# STEERING_WHEEL_SWITCHES_V2_CONTROLLER.net
KiCad netlist of a schematic drawn in Altium Designer
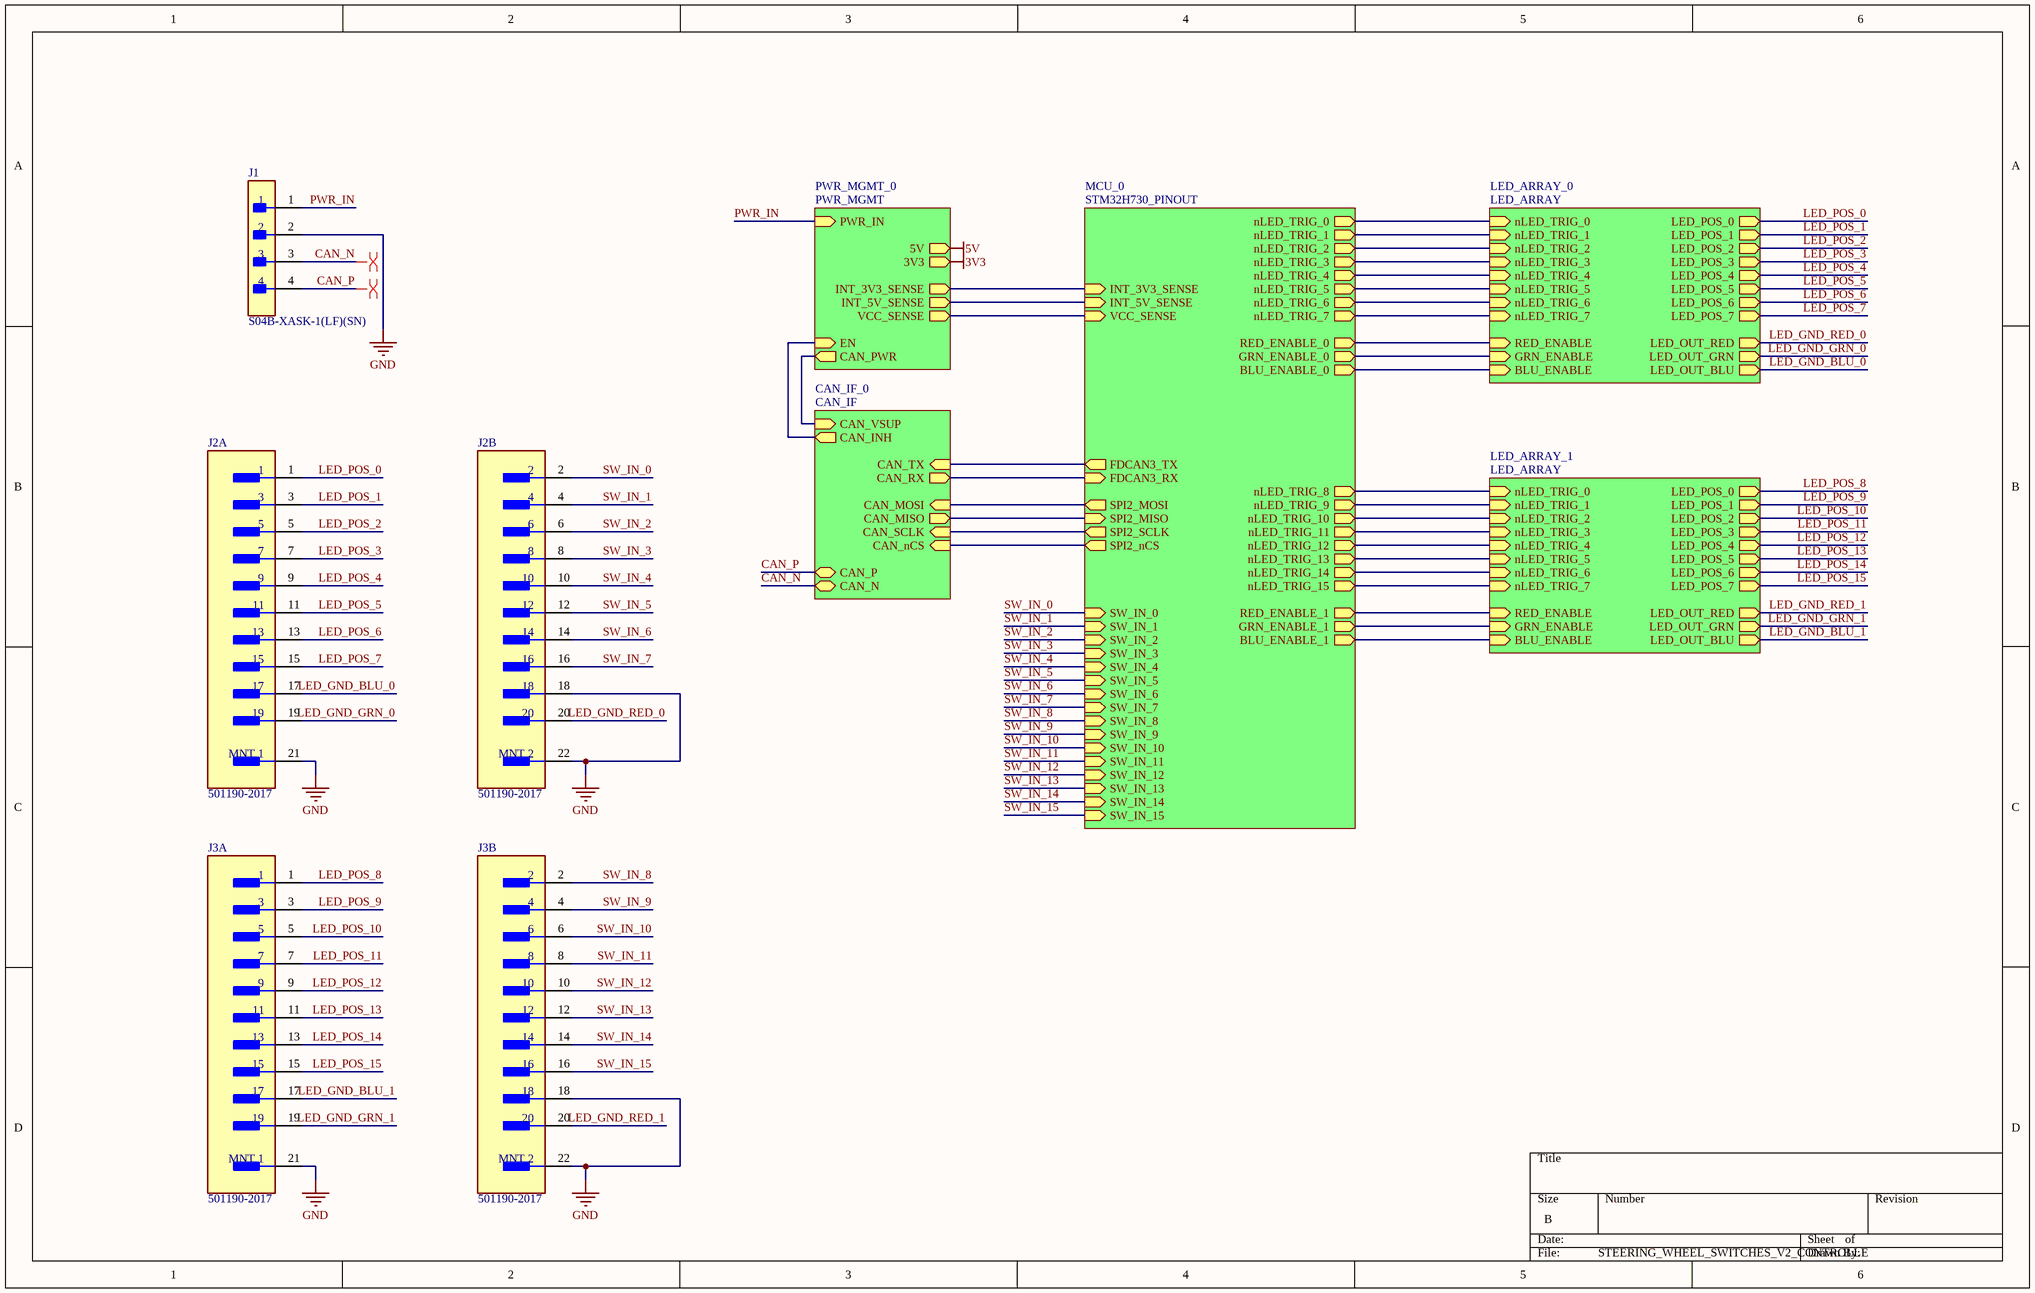
[diagram p0: STEERING_WHEEL_SWITCHES_V2_CONTROLLER.SchDoc]

(export (version "E")
  (design (tool "Eeschema 10.0.6"))
  (components
    (comp (ref "J1")
      (value "S04B-XASK-1(LF)(SN)")
      (footprint "FP-S04B-XASK-1_LF_SN-MFG")
      (description "CONN HEADER R/A 4POS 2.5MM")
      (libsource (lib "Altium Content Vault") (part "299a8cea1bdcbc3624fe62c390fa72c"))
    )
    (comp (ref "J2")
      (value "501190-2017")
      (footprint "FP-501190-2017-MFG")
      (description "CONN HEADER SMD 20POS 1MM")
      (libsource (lib "Altium Content Vault") (part "3088fde206a7053fe950ea66454f304"))
    )
    (comp (ref "J3")
      (value "501190-2017")
      (footprint "FP-501190-2017-MFG")
      (description "CONN HEADER SMD 20POS 1MM")
      (libsource (lib "Altium Content Vault") (part "3088fde206a7053fe950ea66454f304"))
    )
  )
  (nets
    (net (code "5") (name "/CAN_N") (class "Default")
      (node (ref "J1") (pin "3") (pinfunction "3_3") (pintype "passive"))
    )
    (net (code "6") (name "/CAN_P") (class "Default")
      (node (ref "J1") (pin "4") (pinfunction "4_4") (pintype "passive"))
    )
    (net (code "14") (name "/LED_GND_BLU_0") (class "Default")
      (node (ref "J2") (pin "17") (pinfunction "17_17") (pintype "passive"))
    )
    (net (code "15") (name "/LED_GND_BLU_1") (class "Default")
      (node (ref "J3") (pin "17") (pinfunction "17_17") (pintype "passive"))
    )
    (net (code "16") (name "/LED_GND_GRN_0") (class "Default")
      (node (ref "J2") (pin "19") (pinfunction "19_19") (pintype "passive"))
    )
    (net (code "17") (name "/LED_GND_GRN_1") (class "Default")
      (node (ref "J3") (pin "19") (pinfunction "19_19") (pintype "passive"))
    )
    (net (code "18") (name "/LED_GND_RED_0") (class "Default")
      (node (ref "J2") (pin "20") (pinfunction "20_20") (pintype "passive"))
    )
    (net (code "19") (name "/LED_GND_RED_1") (class "Default")
      (node (ref "J3") (pin "20") (pinfunction "20_20") (pintype "passive"))
    )
    (net (code "20") (name "/LED_POS_0") (class "Default")
      (node (ref "J2") (pin "1") (pinfunction "1_1") (pintype "passive"))
    )
    (net (code "21") (name "/LED_POS_1") (class "Default")
      (node (ref "J2") (pin "3") (pinfunction "3_3") (pintype "passive"))
    )
    (net (code "22") (name "/LED_POS_2") (class "Default")
      (node (ref "J2") (pin "5") (pinfunction "5_5") (pintype "passive"))
    )
    (net (code "23") (name "/LED_POS_3") (class "Default")
      (node (ref "J2") (pin "7") (pinfunction "7_7") (pintype "passive"))
    )
    (net (code "24") (name "/LED_POS_4") (class "Default")
      (node (ref "J2") (pin "9") (pinfunction "9_9") (pintype "passive"))
    )
    (net (code "25") (name "/LED_POS_5") (class "Default")
      (node (ref "J2") (pin "11") (pinfunction "11_11") (pintype "passive"))
    )
    (net (code "26") (name "/LED_POS_6") (class "Default")
      (node (ref "J2") (pin "13") (pinfunction "13_13") (pintype "passive"))
    )
    (net (code "27") (name "/LED_POS_7") (class "Default")
      (node (ref "J2") (pin "15") (pinfunction "15_15") (pintype "passive"))
    )
    (net (code "28") (name "/LED_POS_8") (class "Default")
      (node (ref "J3") (pin "1") (pinfunction "1_1") (pintype "passive"))
    )
    (net (code "29") (name "/LED_POS_9") (class "Default")
      (node (ref "J3") (pin "3") (pinfunction "3_3") (pintype "passive"))
    )
    (net (code "30") (name "/LED_POS_10") (class "Default")
      (node (ref "J3") (pin "5") (pinfunction "5_5") (pintype "passive"))
    )
    (net (code "31") (name "/LED_POS_11") (class "Default")
      (node (ref "J3") (pin "7") (pinfunction "7_7") (pintype "passive"))
    )
    (net (code "32") (name "/LED_POS_12") (class "Default")
      (node (ref "J3") (pin "9") (pinfunction "9_9") (pintype "passive"))
    )
    (net (code "33") (name "/LED_POS_13") (class "Default")
      (node (ref "J3") (pin "11") (pinfunction "11_11") (pintype "passive"))
    )
    (net (code "34") (name "/LED_POS_14") (class "Default")
      (node (ref "J3") (pin "13") (pinfunction "13_13") (pintype "passive"))
    )
    (net (code "35") (name "/LED_POS_15") (class "Default")
      (node (ref "J3") (pin "15") (pinfunction "15_15") (pintype "passive"))
    )
    (net (code "36") (name "/PWR_IN") (class "Default")
      (node (ref "J1") (pin "1") (pinfunction "1_1") (pintype "passive"))
    )
    (net (code "42") (name "/SW_IN_0") (class "Default")
      (node (ref "J2") (pin "2") (pinfunction "2_2") (pintype "passive"))
    )
    (net (code "43") (name "/SW_IN_1") (class "Default")
      (node (ref "J2") (pin "4") (pinfunction "4_4") (pintype "passive"))
    )
    (net (code "44") (name "/SW_IN_2") (class "Default")
      (node (ref "J2") (pin "6") (pinfunction "6_6") (pintype "passive"))
    )
    (net (code "45") (name "/SW_IN_3") (class "Default")
      (node (ref "J2") (pin "8") (pinfunction "8_8") (pintype "passive"))
    )
    (net (code "46") (name "/SW_IN_4") (class "Default")
      (node (ref "J2") (pin "10") (pinfunction "10_10") (pintype "passive"))
    )
    (net (code "47") (name "/SW_IN_5") (class "Default")
      (node (ref "J2") (pin "12") (pinfunction "12_12") (pintype "passive"))
    )
    (net (code "48") (name "/SW_IN_6") (class "Default")
      (node (ref "J2") (pin "14") (pinfunction "14_14") (pintype "passive"))
    )
    (net (code "49") (name "/SW_IN_7") (class "Default")
      (node (ref "J2") (pin "16") (pinfunction "16_16") (pintype "passive"))
    )
    (net (code "50") (name "/SW_IN_8") (class "Default")
      (node (ref "J3") (pin "2") (pinfunction "2_2") (pintype "passive"))
    )
    (net (code "51") (name "/SW_IN_9") (class "Default")
      (node (ref "J3") (pin "4") (pinfunction "4_4") (pintype "passive"))
    )
    (net (code "52") (name "/SW_IN_10") (class "Default")
      (node (ref "J3") (pin "6") (pinfunction "6_6") (pintype "passive"))
    )
    (net (code "53") (name "/SW_IN_11") (class "Default")
      (node (ref "J3") (pin "8") (pinfunction "8_8") (pintype "passive"))
    )
    (net (code "54") (name "/SW_IN_12") (class "Default")
      (node (ref "J3") (pin "10") (pinfunction "10_10") (pintype "passive"))
    )
    (net (code "55") (name "/SW_IN_13") (class "Default")
      (node (ref "J3") (pin "12") (pinfunction "12_12") (pintype "passive"))
    )
    (net (code "56") (name "/SW_IN_14") (class "Default")
      (node (ref "J3") (pin "14") (pinfunction "14_14") (pintype "passive"))
    )
    (net (code "57") (name "/SW_IN_15") (class "Default")
      (node (ref "J3") (pin "16") (pinfunction "16_16") (pintype "passive"))
    )
    (net (code "77") (name "GND") (class "Default")
      (node (ref "J1") (pin "2") (pinfunction "2_2") (pintype "passive"))
      (node (ref "J2") (pin "18") (pinfunction "18_18") (pintype "passive"))
      (node (ref "J2") (pin "21") (pinfunction "MNT_1_21") (pintype "passive"))
      (node (ref "J2") (pin "22") (pinfunction "MNT_2_22") (pintype "passive"))
      (node (ref "J3") (pin "18") (pinfunction "18_18") (pintype "passive"))
      (node (ref "J3") (pin "21") (pinfunction "MNT_1_21") (pintype "passive"))
      (node (ref "J3") (pin "22") (pinfunction "MNT_2_22") (pintype "passive"))
    )
  )
)
